# 2x6x1_27mm-pogo-adapter-flipped-mk-1_0_1.net
KiCad netlist of a schematic drawn in EAGLE
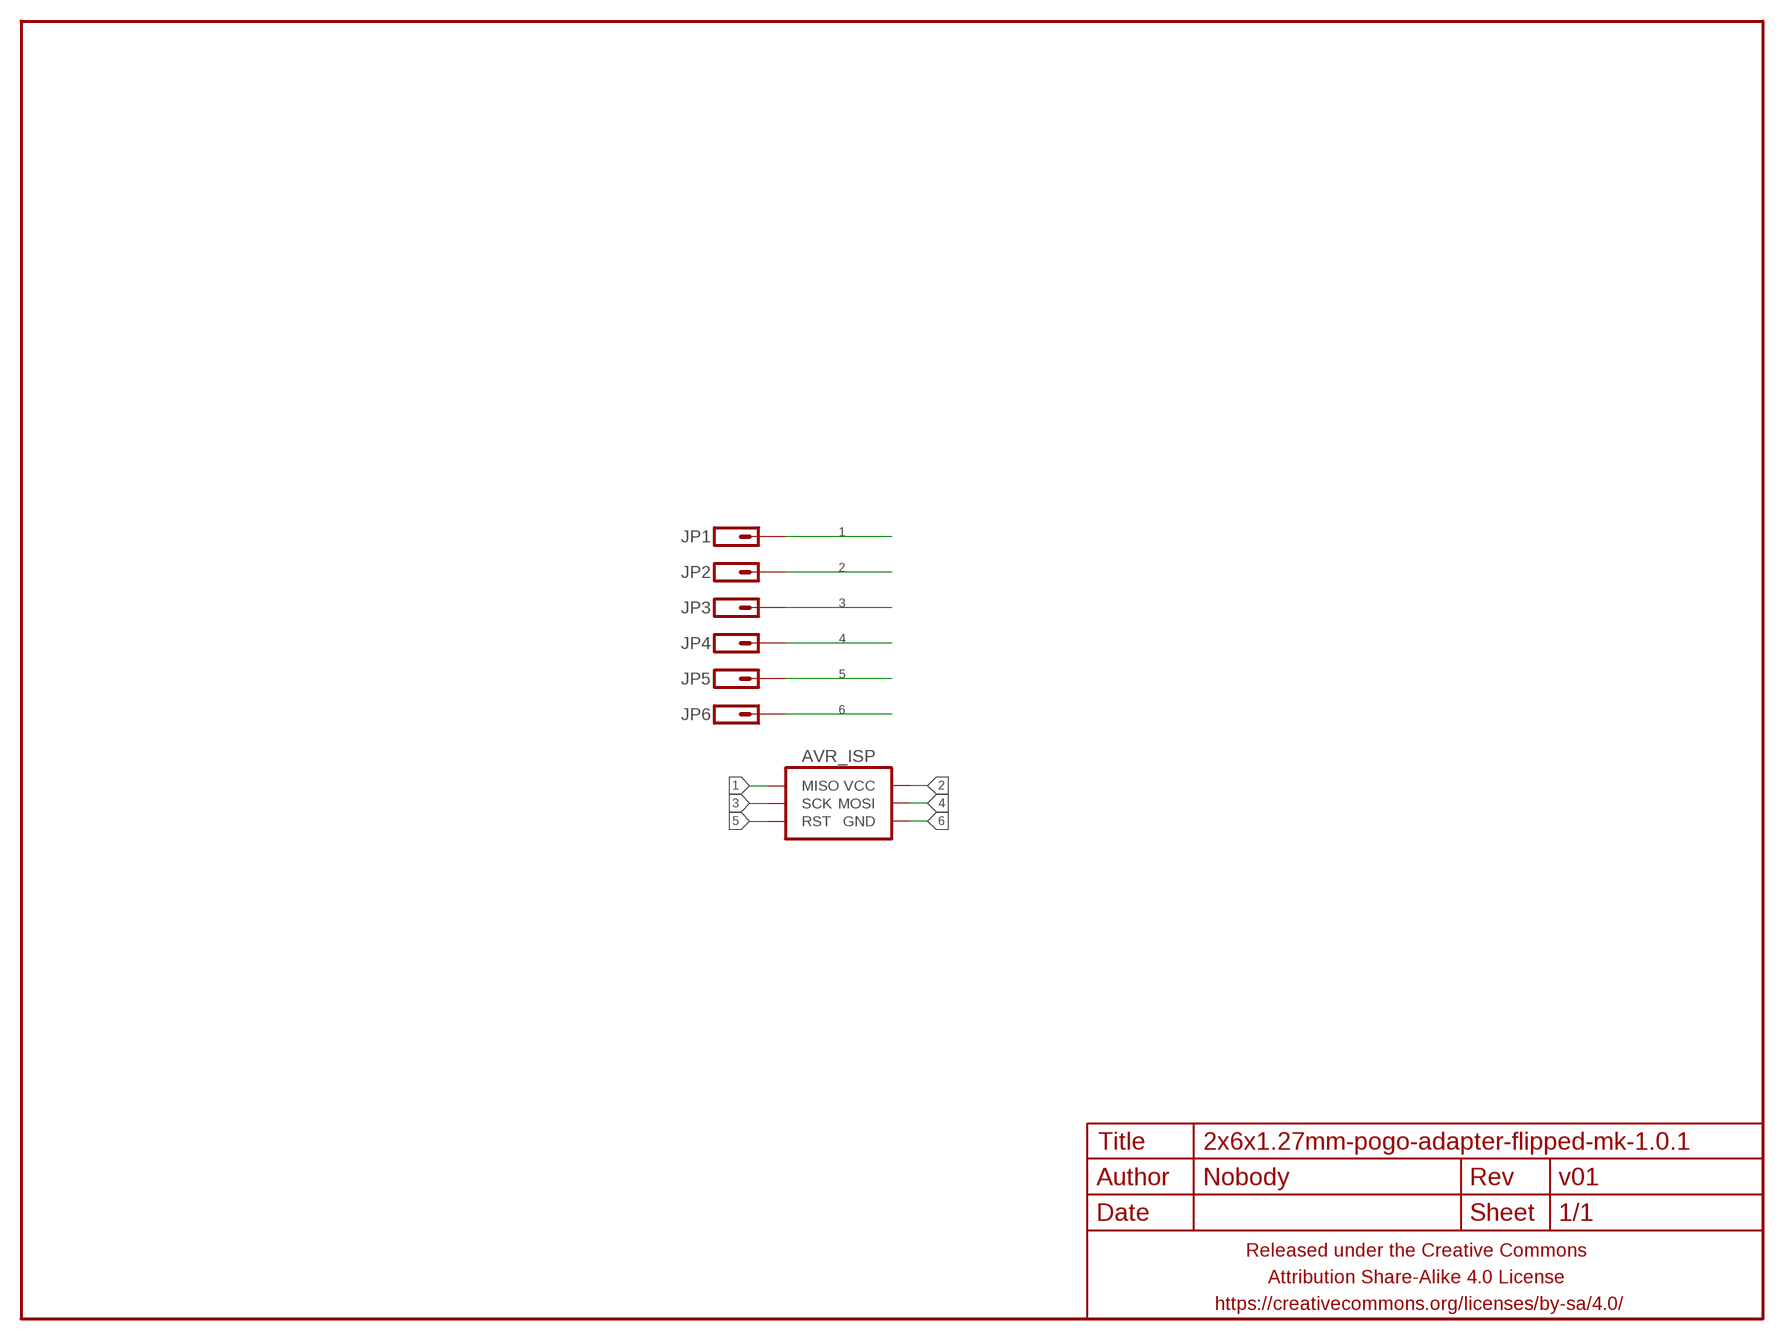
[diagram p0: schematic, sheet 1]

(export (version "E")
  (design (tool "Eeschema 10.0.6"))
  (components
    (comp (ref "AVR_ISP")
      (value "AVR_SPI_PRG_62X3_SMD")
      (footprint "eagle-import:2X3_SMD")
      (libsource (lib "eagle-import") (part "AVR_SPI_PRG_62X3_SMD"))
    )
    (comp (ref "FRAME1")
      (value "FRAME-LETTERNO_PACKAGE")
      (footprint "eagle-import:DUMMY")
      (fields (field (name "DESIGNER") "Nobody") (field (name "VERSION") "v01"))
      (libsource (lib "eagle-import") (part "FRAME-LETTERNO_PACKAGE"))
    )
    (comp (ref "JP1")
      (value "M01PTH-0.7MM-CIR-NS")
      (footprint "eagle-import:1X01-0.7MM-CIR-NS")
      (libsource (lib "eagle-import") (part "M01PTH-0.7MM-CIR-NS"))
    )
    (comp (ref "JP2")
      (value "M01PTH-0.7MM-CIR-NS")
      (footprint "eagle-import:1X01-0.7MM-CIR-NS")
      (libsource (lib "eagle-import") (part "M01PTH-0.7MM-CIR-NS"))
    )
    (comp (ref "JP3")
      (value "M01PTH-0.7MM-CIR-NS")
      (footprint "eagle-import:1X01-0.7MM-CIR-NS")
      (libsource (lib "eagle-import") (part "M01PTH-0.7MM-CIR-NS"))
    )
    (comp (ref "JP4")
      (value "M01PTH-0.7MM-CIR-NS")
      (footprint "eagle-import:1X01-0.7MM-CIR-NS")
      (libsource (lib "eagle-import") (part "M01PTH-0.7MM-CIR-NS"))
    )
    (comp (ref "JP5")
      (value "M01PTH-0.7MM-CIR-NS")
      (footprint "eagle-import:1X01-0.7MM-CIR-NS")
      (libsource (lib "eagle-import") (part "M01PTH-0.7MM-CIR-NS"))
    )
    (comp (ref "JP6")
      (value "M01PTH-0.7MM-CIR-NS")
      (footprint "eagle-import:1X01-0.7MM-CIR-NS")
      (libsource (lib "eagle-import") (part "M01PTH-0.7MM-CIR-NS"))
    )
  )
  (nets
    (net (code "1") (name "1") (class "Default")
      (node (ref "AVR_ISP") (pin "1") (pinfunction "MISO_1") (pintype "passive"))
      (node (ref "JP1") (pin "P$1") (pinfunction "1_P$1") (pintype "passive"))
    )
    (net (code "2") (name "2") (class "Default")
      (node (ref "AVR_ISP") (pin "2") (pinfunction "VCC_2") (pintype "passive"))
      (node (ref "JP2") (pin "P$1") (pinfunction "1_P$1") (pintype "passive"))
    )
    (net (code "3") (name "3") (class "Default")
      (node (ref "AVR_ISP") (pin "3") (pinfunction "SCK_3") (pintype "passive"))
      (node (ref "JP3") (pin "P$1") (pinfunction "1_P$1") (pintype "passive"))
    )
    (net (code "4") (name "4") (class "Default")
      (node (ref "AVR_ISP") (pin "4") (pinfunction "MOSI_4") (pintype "passive"))
      (node (ref "JP4") (pin "P$1") (pinfunction "1_P$1") (pintype "passive"))
    )
    (net (code "5") (name "5") (class "Default")
      (node (ref "AVR_ISP") (pin "5") (pinfunction "RST_5") (pintype "passive"))
      (node (ref "JP5") (pin "P$1") (pinfunction "1_P$1") (pintype "passive"))
    )
    (net (code "6") (name "6") (class "Default")
      (node (ref "AVR_ISP") (pin "6") (pinfunction "GND_6") (pintype "passive"))
      (node (ref "JP6") (pin "P$1") (pinfunction "1_P$1") (pintype "passive"))
    )
  )
)
